# CitizenBoard_V3_2.net
KiCad netlist of a schematic drawn in EAGLE
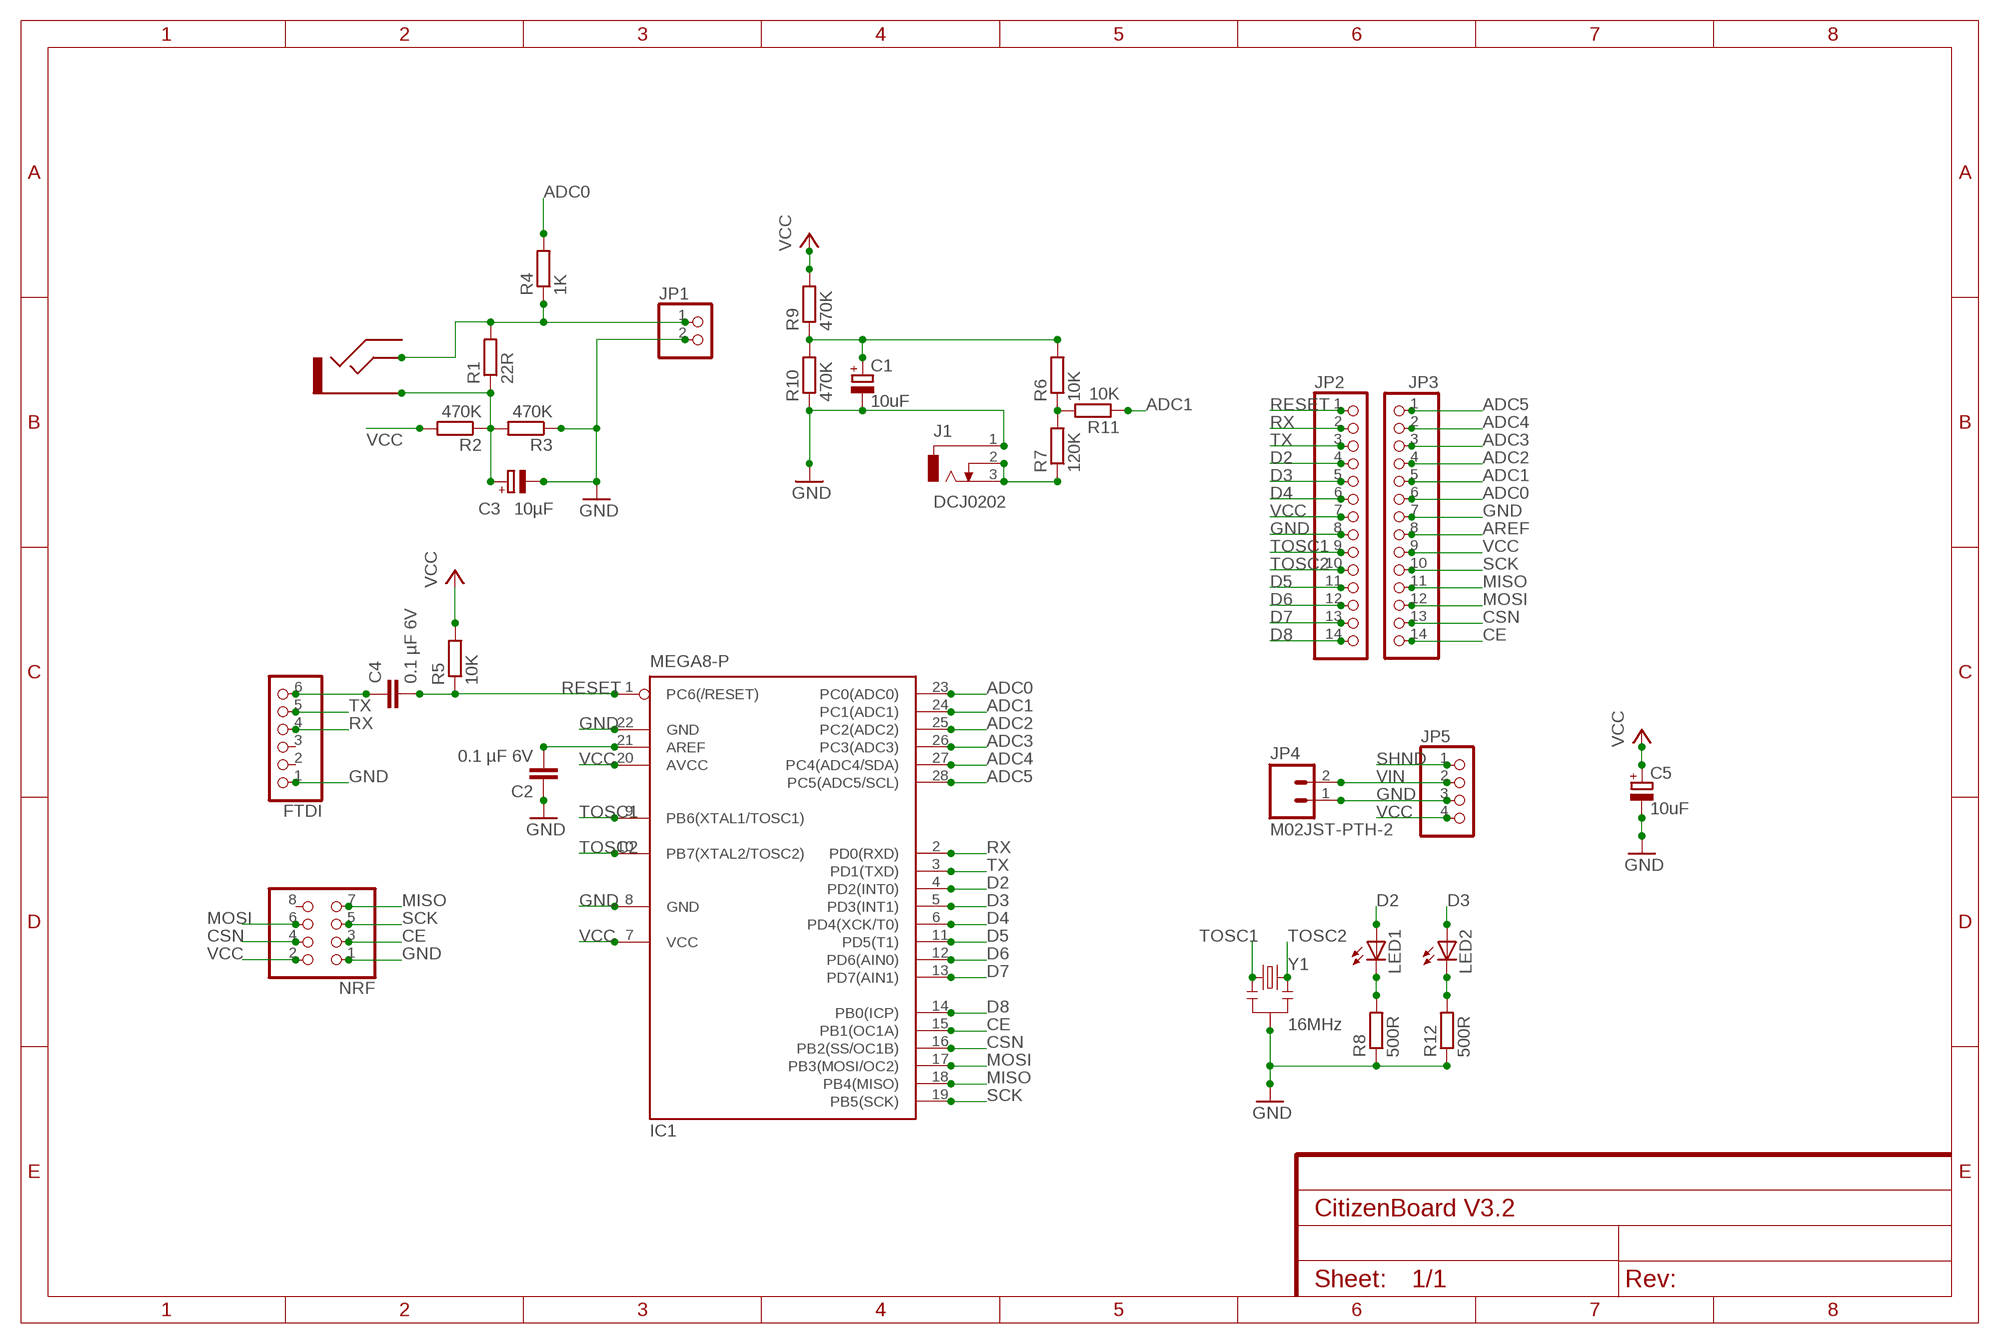
[diagram p0: schematic, sheet 1]

(export (version "E")
  (design (tool "Eeschema 10.0.6"))
  (components
    (comp (ref "C1")
      (value "10uF")
      (footprint "eagle-import:E2,5-6E")
      (libsource (lib "eagle-import") (part "CPOL-EUE2,5-6E"))
    )
    (comp (ref "C2")
      (value "0.1 µF 6V")
      (footprint "eagle-import:C025-024X044")
      (libsource (lib "eagle-import") (part "C-EU025-024X044"))
    )
    (comp (ref "C3")
      (value "10µF")
      (footprint "eagle-import:E2,5-6E")
      (libsource (lib "eagle-import") (part "CPOL-EUE2,5-6E"))
    )
    (comp (ref "C4")
      (value "0.1 µF 6V")
      (footprint "eagle-import:C025-024X044")
      (libsource (lib "eagle-import") (part "C-EU025-024X044"))
    )
    (comp (ref "C5")
      (value "10uF")
      (footprint "eagle-import:E2,5-6E")
      (libsource (lib "eagle-import") (part "CPOL-EUE2,5-6E"))
    )
    (comp (ref "FTDI")
      (value "PINHD-1X6")
      (footprint "eagle-import:1X06")
      (libsource (lib "eagle-import") (part "PINHD-1X6"))
    )
    (comp (ref "IC1")
      (value "MEGA8-P")
      (footprint "eagle-import:DIL28-3")
      (libsource (lib "eagle-import") (part "MEGA8-P"))
    )
    (comp (ref "J1")
      (value "DCJ0202")
      (footprint "eagle-import:DCJ0202")
      (libsource (lib "eagle-import") (part "DCJ0202"))
    )
    (comp (ref "J2")
      (value "AUDIO-JACK-3.5")
      (footprint "eagle-import:AUDIO-JACK-3.5")
      (libsource (lib "eagle-import") (part "AUDIO-JACK-3.5"))
    )
    (comp (ref "JP1")
      (value "PINHD-1X2")
      (footprint "eagle-import:1X02")
      (libsource (lib "eagle-import") (part "PINHD-1X2"))
    )
    (comp (ref "JP2")
      (value "PINHD-1X14")
      (footprint "eagle-import:1X14")
      (libsource (lib "eagle-import") (part "PINHD-1X14"))
    )
    (comp (ref "JP3")
      (value "PINHD-1X14")
      (footprint "eagle-import:1X14")
      (libsource (lib "eagle-import") (part "PINHD-1X14"))
    )
    (comp (ref "JP4")
      (value "M02JST-PTH-2")
      (footprint "eagle-import:JST-2-PTH")
      (libsource (lib "eagle-import") (part "M02JST-PTH-2"))
    )
    (comp (ref "JP5")
      (value "PINHD-1X4")
      (footprint "eagle-import:1X04")
      (libsource (lib "eagle-import") (part "PINHD-1X4"))
    )
    (comp (ref "LED1")
      (value "LED3MM")
      (footprint "eagle-import:LED3MM")
      (libsource (lib "eagle-import") (part "LED3MM"))
    )
    (comp (ref "LED2")
      (value "LED3MM")
      (footprint "eagle-import:LED3MM")
      (libsource (lib "eagle-import") (part "LED3MM"))
    )
    (comp (ref "NRF")
      (value "PINHD-2X4")
      (footprint "eagle-import:2X04")
      (libsource (lib "eagle-import") (part "PINHD-2X4"))
    )
    (comp (ref "R1")
      (value "22R")
      (footprint "eagle-import:0204_7")
      (libsource (lib "eagle-import") (part "R-EU_0204/7"))
    )
    (comp (ref "R2")
      (value "470K")
      (footprint "eagle-import:0204_7")
      (libsource (lib "eagle-import") (part "R-EU_0204/7"))
    )
    (comp (ref "R3")
      (value "470K")
      (footprint "eagle-import:0204_7")
      (libsource (lib "eagle-import") (part "R-EU_0204/7"))
    )
    (comp (ref "R4")
      (value "1K")
      (footprint "eagle-import:0204_7")
      (libsource (lib "eagle-import") (part "R-EU_0204/7"))
    )
    (comp (ref "R5")
      (value "10K")
      (footprint "eagle-import:0204_7")
      (libsource (lib "eagle-import") (part "R-EU_0204/7"))
    )
    (comp (ref "R6")
      (value "10K")
      (footprint "eagle-import:0204_7")
      (libsource (lib "eagle-import") (part "R-EU_0204/7"))
    )
    (comp (ref "R7")
      (value "120K")
      (footprint "eagle-import:0204_7")
      (libsource (lib "eagle-import") (part "R-EU_0204/7"))
    )
    (comp (ref "R8")
      (value "500R")
      (footprint "eagle-import:0204_7")
      (libsource (lib "eagle-import") (part "R-EU_0204/7"))
    )
    (comp (ref "R9")
      (value "470K")
      (footprint "eagle-import:0204_7")
      (libsource (lib "eagle-import") (part "R-EU_0204/7"))
    )
    (comp (ref "R10")
      (value "470K")
      (footprint "eagle-import:0204_7")
      (libsource (lib "eagle-import") (part "R-EU_0204/7"))
    )
    (comp (ref "R11")
      (value "10K")
      (footprint "eagle-import:0204_7")
      (libsource (lib "eagle-import") (part "R-EU_0204/7"))
    )
    (comp (ref "R12")
      (value "500R")
      (footprint "eagle-import:0204_7")
      (libsource (lib "eagle-import") (part "R-EU_0204/7"))
    )
    (comp (ref "Y1")
      (value "16MHz")
      (footprint "eagle-import:RESONATOR-PTH")
      (libsource (lib "eagle-import") (part "RESONATORPTH"))
    )
  )
  (nets
    (net (code "1") (name "/ADC0") (class "Default")
      (node (ref "IC1") (pin "23") (pinfunction "PC0(ADC0)_23") (pintype "bidirectional"))
      (node (ref "JP3") (pin "6") (pinfunction "6_6") (pintype "passive"))
      (node (ref "R4") (pin "2") (pinfunction "2_2") (pintype "passive"))
    )
    (net (code "2") (name "/ADC1") (class "Default")
      (node (ref "IC1") (pin "24") (pinfunction "PC1(ADC1)_24") (pintype "bidirectional"))
      (node (ref "JP3") (pin "5") (pinfunction "5_5") (pintype "passive"))
      (node (ref "R11") (pin "1") (pinfunction "1_1") (pintype "passive"))
    )
    (net (code "3") (name "/ADC2") (class "Default")
      (node (ref "IC1") (pin "25") (pinfunction "PC2(ADC2)_25") (pintype "bidirectional"))
      (node (ref "JP3") (pin "4") (pinfunction "4_4") (pintype "passive"))
    )
    (net (code "4") (name "/ADC3") (class "Default")
      (node (ref "IC1") (pin "26") (pinfunction "PC3(ADC3)_26") (pintype "bidirectional"))
      (node (ref "JP3") (pin "3") (pinfunction "3_3") (pintype "passive"))
    )
    (net (code "5") (name "/ADC4") (class "Default")
      (node (ref "IC1") (pin "27") (pinfunction "PC4(ADC4/SDA)_27") (pintype "bidirectional"))
      (node (ref "JP3") (pin "2") (pinfunction "2_2") (pintype "passive"))
    )
    (net (code "6") (name "/ADC5") (class "Default")
      (node (ref "IC1") (pin "28") (pinfunction "PC5(ADC5/SCL)_28") (pintype "bidirectional"))
      (node (ref "JP3") (pin "1") (pinfunction "1_1") (pintype "passive"))
    )
    (net (code "7") (name "/AREF") (class "Default")
      (node (ref "C2") (pin "2") (pinfunction "2_2") (pintype "passive"))
      (node (ref "IC1") (pin "21") (pinfunction "AREF_21") (pintype "passive"))
      (node (ref "JP3") (pin "8") (pinfunction "8_8") (pintype "passive"))
    )
    (net (code "8") (name "/CE") (class "Default")
      (node (ref "IC1") (pin "15") (pinfunction "PB1(OC1A)_15") (pintype "bidirectional"))
      (node (ref "JP3") (pin "14") (pinfunction "14_14") (pintype "passive"))
      (node (ref "NRF") (pin "3") (pinfunction "3_3") (pintype "passive"))
    )
    (net (code "9") (name "/CSN") (class "Default")
      (node (ref "IC1") (pin "16") (pinfunction "PB2(SS/OC1B)_16") (pintype "bidirectional"))
      (node (ref "JP3") (pin "13") (pinfunction "13_13") (pintype "passive"))
      (node (ref "NRF") (pin "4") (pinfunction "4_4") (pintype "passive"))
    )
    (net (code "10") (name "/D2") (class "Default")
      (node (ref "IC1") (pin "4") (pinfunction "PD2(INT0)_4") (pintype "bidirectional"))
      (node (ref "JP2") (pin "4") (pinfunction "4_4") (pintype "passive"))
      (node (ref "LED1") (pin "A") (pinfunction "A_A") (pintype "passive"))
    )
    (net (code "11") (name "/D3") (class "Default")
      (node (ref "IC1") (pin "5") (pinfunction "PD3(INT1)_5") (pintype "bidirectional"))
      (node (ref "JP2") (pin "5") (pinfunction "5_5") (pintype "passive"))
      (node (ref "LED2") (pin "A") (pinfunction "A_A") (pintype "passive"))
    )
    (net (code "12") (name "/D4") (class "Default")
      (node (ref "IC1") (pin "6") (pinfunction "PD4(XCK/T0)_6") (pintype "bidirectional"))
      (node (ref "JP2") (pin "6") (pinfunction "6_6") (pintype "passive"))
    )
    (net (code "13") (name "/D5") (class "Default")
      (node (ref "IC1") (pin "11") (pinfunction "PD5(T1)_11") (pintype "bidirectional"))
      (node (ref "JP2") (pin "11") (pinfunction "11_11") (pintype "passive"))
    )
    (net (code "14") (name "/D6") (class "Default")
      (node (ref "IC1") (pin "12") (pinfunction "PD6(AIN0)_12") (pintype "bidirectional"))
      (node (ref "JP2") (pin "12") (pinfunction "12_12") (pintype "passive"))
    )
    (net (code "15") (name "/D7") (class "Default")
      (node (ref "IC1") (pin "13") (pinfunction "PD7(AIN1)_13") (pintype "bidirectional"))
      (node (ref "JP2") (pin "13") (pinfunction "13_13") (pintype "passive"))
    )
    (net (code "16") (name "/D8") (class "Default")
      (node (ref "IC1") (pin "14") (pinfunction "PB0(ICP)_14") (pintype "bidirectional"))
      (node (ref "JP2") (pin "14") (pinfunction "14_14") (pintype "passive"))
    )
    (net (code "17") (name "/MISO") (class "Default")
      (node (ref "IC1") (pin "18") (pinfunction "PB4(MISO)_18") (pintype "bidirectional"))
      (node (ref "JP3") (pin "11") (pinfunction "11_11") (pintype "passive"))
      (node (ref "NRF") (pin "7") (pinfunction "7_7") (pintype "passive"))
    )
    (net (code "18") (name "/MOSI") (class "Default")
      (node (ref "IC1") (pin "17") (pinfunction "PB3(MOSI/OC2)_17") (pintype "bidirectional"))
      (node (ref "JP3") (pin "12") (pinfunction "12_12") (pintype "passive"))
      (node (ref "NRF") (pin "6") (pinfunction "6_6") (pintype "passive"))
    )
    (net (code "19") (name "/RESET") (class "Default")
      (node (ref "C4") (pin "2") (pinfunction "2_2") (pintype "passive"))
      (node (ref "IC1") (pin "1") (pinfunction "PC6(/RESET)_1") (pintype "bidirectional"))
      (node (ref "JP2") (pin "1") (pinfunction "1_1") (pintype "passive"))
      (node (ref "R5") (pin "1") (pinfunction "1_1") (pintype "passive"))
    )
    (net (code "20") (name "/RX") (class "Default")
      (node (ref "FTDI") (pin "4") (pinfunction "4_4") (pintype "passive"))
      (node (ref "IC1") (pin "2") (pinfunction "PD0(RXD)_2") (pintype "bidirectional"))
      (node (ref "JP2") (pin "2") (pinfunction "2_2") (pintype "passive"))
    )
    (net (code "21") (name "/SCK") (class "Default")
      (node (ref "IC1") (pin "19") (pinfunction "PB5(SCK)_19") (pintype "bidirectional"))
      (node (ref "JP3") (pin "10") (pinfunction "10_10") (pintype "passive"))
      (node (ref "NRF") (pin "5") (pinfunction "5_5") (pintype "passive"))
    )
    (net (code "22") (name "/SHND") (class "Default")
      (node (ref "JP5") (pin "1") (pinfunction "1_1") (pintype "passive"))
    )
    (net (code "23") (name "/TOSC1") (class "Default")
      (node (ref "IC1") (pin "9") (pinfunction "PB6(XTAL1/TOSC1)_9") (pintype "bidirectional"))
      (node (ref "JP2") (pin "9") (pinfunction "9_9") (pintype "passive"))
      (node (ref "Y1") (pin "1") (pinfunction "1_1") (pintype "passive"))
    )
    (net (code "24") (name "/TOSC2") (class "Default")
      (node (ref "IC1") (pin "10") (pinfunction "PB7(XTAL2/TOSC2)_10") (pintype "bidirectional"))
      (node (ref "JP2") (pin "10") (pinfunction "10_10") (pintype "passive"))
      (node (ref "Y1") (pin "3") (pinfunction "3_3") (pintype "passive"))
    )
    (net (code "25") (name "/TX") (class "Default")
      (node (ref "FTDI") (pin "5") (pinfunction "5_5") (pintype "passive"))
      (node (ref "IC1") (pin "3") (pinfunction "PD1(TXD)_3") (pintype "bidirectional"))
      (node (ref "JP2") (pin "3") (pinfunction "3_3") (pintype "passive"))
    )
    (net (code "26") (name "/VIN") (class "Default")
      (node (ref "JP4") (pin "2") (pinfunction "2_2") (pintype "passive"))
      (node (ref "JP5") (pin "2") (pinfunction "2_2") (pintype "passive"))
    )
    (net (code "27") (name "GND") (class "Default")
      (node (ref "C1") (pin "-") (pinfunction "-_-") (pintype "passive"))
      (node (ref "C2") (pin "1") (pinfunction "1_1") (pintype "passive"))
      (node (ref "C3") (pin "-") (pinfunction "-_-") (pintype "passive"))
      (node (ref "C5") (pin "-") (pinfunction "-_-") (pintype "passive"))
      (node (ref "FTDI") (pin "1") (pinfunction "1_1") (pintype "passive"))
      (node (ref "IC1") (pin "22") (pinfunction "GND_22") (pintype "power_in"))
      (node (ref "IC1") (pin "8") (pinfunction "GND_8") (pintype "power_in"))
      (node (ref "J1") (pin "1") (pinfunction "1_1") (pintype "passive"))
      (node (ref "JP1") (pin "2") (pinfunction "2_2") (pintype "passive"))
      (node (ref "JP2") (pin "8") (pinfunction "8_8") (pintype "passive"))
      (node (ref "JP3") (pin "7") (pinfunction "7_7") (pintype "passive"))
      (node (ref "JP4") (pin "1") (pinfunction "1_1") (pintype "passive"))
      (node (ref "JP5") (pin "3") (pinfunction "3_3") (pintype "passive"))
      (node (ref "NRF") (pin "1") (pinfunction "1_1") (pintype "passive"))
      (node (ref "R10") (pin "1") (pinfunction "1_1") (pintype "passive"))
      (node (ref "R12") (pin "1") (pinfunction "1_1") (pintype "passive"))
      (node (ref "R3") (pin "1") (pinfunction "1_1") (pintype "passive"))
      (node (ref "R8") (pin "1") (pinfunction "1_1") (pintype "passive"))
      (node (ref "Y1") (pin "2") (pinfunction "2_2") (pintype "passive"))
    )
    (net (code "28") (name "Net-(C1-Pad+)") (class "Default")
      (node (ref "C1") (pin "+") (pinfunction "+_+") (pintype "passive"))
      (node (ref "R10") (pin "2") (pinfunction "2_2") (pintype "passive"))
      (node (ref "R6") (pin "2") (pinfunction "2_2") (pintype "passive"))
      (node (ref "R9") (pin "1") (pinfunction "1_1") (pintype "passive"))
    )
    (net (code "29") (name "Net-(C4-Pad1)") (class "Default")
      (node (ref "C4") (pin "1") (pinfunction "1_1") (pintype "passive"))
      (node (ref "FTDI") (pin "6") (pinfunction "6_6") (pintype "passive"))
    )
    (net (code "30") (name "Net-(J1-Pad2)") (class "Default")
      (node (ref "J1") (pin "2") (pinfunction "2_2") (pintype "passive"))
      (node (ref "J1") (pin "3") (pinfunction "3_3") (pintype "passive"))
      (node (ref "R7") (pin "1") (pinfunction "1_1") (pintype "passive"))
    )
    (net (code "31") (name "Net-(J2-GND)") (class "Default")
      (node (ref "C3") (pin "+") (pinfunction "+_+") (pintype "passive"))
      (node (ref "J2") (pin "1S") (pinfunction "GND_1S") (pintype "bidirectional"))
      (node (ref "R1") (pin "1") (pinfunction "1_1") (pintype "passive"))
      (node (ref "R2") (pin "1") (pinfunction "1_1") (pintype "passive"))
      (node (ref "R3") (pin "2") (pinfunction "2_2") (pintype "passive"))
    )
    (net (code "32") (name "Net-(J2-L)") (class "Default")
      (node (ref "J2") (pin "5T") (pinfunction "L_5T") (pintype "bidirectional"))
      (node (ref "JP1") (pin "1") (pinfunction "1_1") (pintype "passive"))
      (node (ref "R1") (pin "2") (pinfunction "2_2") (pintype "passive"))
      (node (ref "R4") (pin "1") (pinfunction "1_1") (pintype "passive"))
    )
    (net (code "33") (name "Net-(LED1-C)") (class "Default")
      (node (ref "LED1") (pin "K") (pinfunction "C_K") (pintype "passive"))
      (node (ref "R8") (pin "2") (pinfunction "2_2") (pintype "passive"))
    )
    (net (code "34") (name "Net-(LED2-C)") (class "Default")
      (node (ref "LED2") (pin "K") (pinfunction "C_K") (pintype "passive"))
      (node (ref "R12") (pin "2") (pinfunction "2_2") (pintype "passive"))
    )
    (net (code "35") (name "Net-(R11-Pad2)") (class "Default")
      (node (ref "R11") (pin "2") (pinfunction "2_2") (pintype "passive"))
      (node (ref "R6") (pin "1") (pinfunction "1_1") (pintype "passive"))
      (node (ref "R7") (pin "2") (pinfunction "2_2") (pintype "passive"))
    )
    (net (code "36") (name "VCC") (class "Default")
      (node (ref "C5") (pin "+") (pinfunction "+_+") (pintype "passive"))
      (node (ref "IC1") (pin "20") (pinfunction "AVCC_20") (pintype "power_in"))
      (node (ref "IC1") (pin "7") (pinfunction "VCC_7") (pintype "power_in"))
      (node (ref "JP2") (pin "7") (pinfunction "7_7") (pintype "passive"))
      (node (ref "JP3") (pin "9") (pinfunction "9_9") (pintype "passive"))
      (node (ref "JP5") (pin "4") (pinfunction "4_4") (pintype "passive"))
      (node (ref "NRF") (pin "2") (pinfunction "2_2") (pintype "passive"))
      (node (ref "R2") (pin "2") (pinfunction "2_2") (pintype "passive"))
      (node (ref "R5") (pin "2") (pinfunction "2_2") (pintype "passive"))
      (node (ref "R9") (pin "2") (pinfunction "2_2") (pintype "passive"))
    )
    (net (code "37") (name "unconnected-(FTDI-Pad2)") (class "Default")
      (node (ref "FTDI") (pin "2") (pinfunction "2_2") (pintype "passive"))
    )
    (net (code "38") (name "unconnected-(FTDI-Pad3)") (class "Default")
      (node (ref "FTDI") (pin "3") (pinfunction "3_3") (pintype "passive"))
    )
    (net (code "39") (name "unconnected-(J2-R-Pad2R)") (class "Default")
      (node (ref "J2") (pin "2R") (pinfunction "R_2R") (pintype "bidirectional"))
    )
    (net (code "40") (name "unconnected-(NRF-Pad8)") (class "Default")
      (node (ref "NRF") (pin "8") (pinfunction "8_8") (pintype "passive"))
    )
  )
)
